# adc-optical.net
KiCad netlist of a schematic drawn in Altium Designer
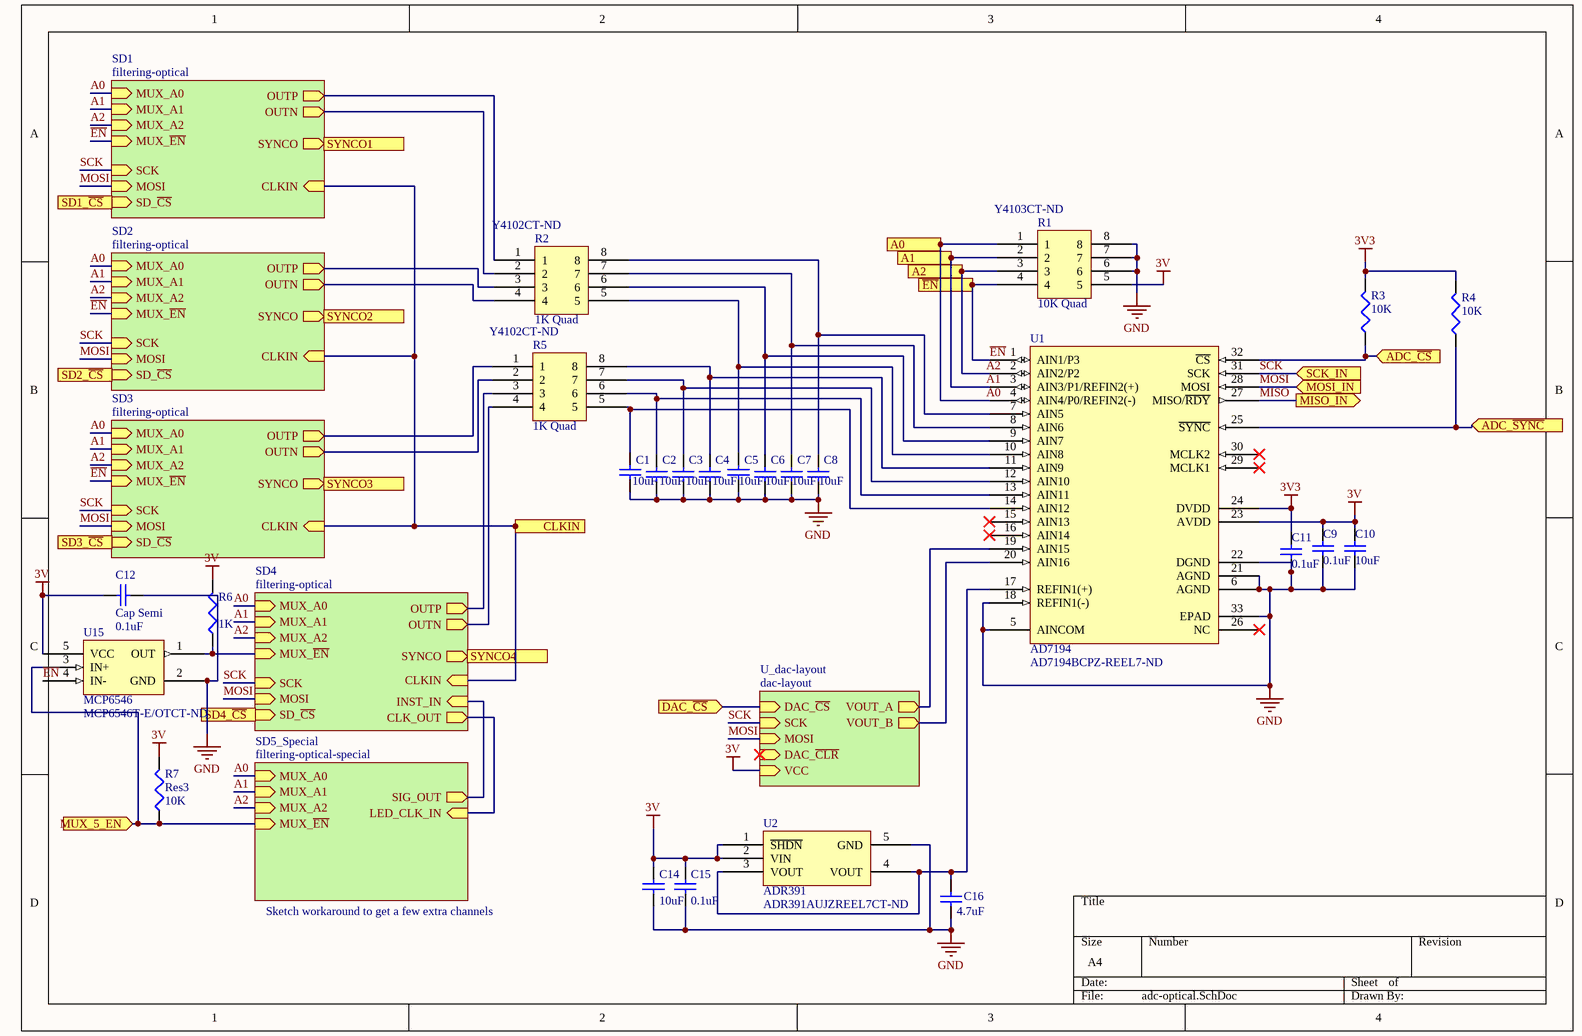
[diagram p0: adc-optical.SchDoc]

(export (version "E")
  (design (tool "Eeschema 10.0.6"))
  (components
    (comp (ref "C1")
      (value "10uF")
      (footprint "1608[0603]")
      (description "Capacitor (Semiconductor SIM Model)")
      (fields (field (name "PUBLISHER") "Altium Limited"))
      (libsource (lib "Miscellaneous Devices") (part "Cap Semi"))
    )
    (comp (ref "C2")
      (value "10uF")
      (footprint "1608[0603]")
      (description "Capacitor (Semiconductor SIM Model)")
      (fields (field (name "PUBLISHER") "Altium Limited"))
      (libsource (lib "Miscellaneous Devices") (part "Cap Semi"))
    )
    (comp (ref "C3")
      (value "10uF")
      (footprint "1608[0603]")
      (description "Capacitor (Semiconductor SIM Model)")
      (fields (field (name "PUBLISHER") "Altium Limited"))
      (libsource (lib "Miscellaneous Devices") (part "Cap Semi"))
    )
    (comp (ref "C4")
      (value "10uF")
      (footprint "1608[0603]")
      (description "Capacitor (Semiconductor SIM Model)")
      (fields (field (name "PUBLISHER") "Altium Limited"))
      (libsource (lib "Miscellaneous Devices") (part "Cap Semi"))
    )
    (comp (ref "C5")
      (value "10uF")
      (footprint "1608[0603]")
      (description "Capacitor (Semiconductor SIM Model)")
      (fields (field (name "PUBLISHER") "Altium Limited"))
      (libsource (lib "Miscellaneous Devices") (part "Cap Semi"))
    )
    (comp (ref "C6")
      (value "10uF")
      (footprint "1608[0603]")
      (description "Capacitor (Semiconductor SIM Model)")
      (fields (field (name "PUBLISHER") "Altium Limited"))
      (libsource (lib "Miscellaneous Devices") (part "Cap Semi"))
    )
    (comp (ref "C7")
      (value "10uF")
      (footprint "1608[0603]")
      (description "Capacitor (Semiconductor SIM Model)")
      (fields (field (name "PUBLISHER") "Altium Limited"))
      (libsource (lib "Miscellaneous Devices") (part "Cap Semi"))
    )
    (comp (ref "C8")
      (value "10uF")
      (footprint "1608[0603]")
      (description "Capacitor (Semiconductor SIM Model)")
      (fields (field (name "PUBLISHER") "Altium Limited"))
      (libsource (lib "Miscellaneous Devices") (part "Cap Semi"))
    )
    (comp (ref "C9")
      (value "0.1uF")
      (footprint "0402")
      (description "Capacitor (Semiconductor SIM Model)")
      (fields (field (name "PUBLISHER") "Altium Limited"))
      (libsource (lib "Miscellaneous Devices") (part "Cap Semi"))
    )
    (comp (ref "C10")
      (value "10uF")
      (footprint "1608[0603]")
      (description "Capacitor (Semiconductor SIM Model)")
      (fields (field (name "PUBLISHER") "Altium Limited"))
      (libsource (lib "Miscellaneous Devices") (part "Cap Semi"))
    )
    (comp (ref "C11")
      (value "0.1uF")
      (footprint "0402")
      (description "Capacitor (Semiconductor SIM Model)")
      (fields (field (name "PUBLISHER") "Altium Limited"))
      (libsource (lib "Miscellaneous Devices") (part "Cap Semi"))
    )
    (comp (ref "C12")
      (value "Cap Semi")
      (footprint "0402")
      (description "Capacitor (Semiconductor SIM Model)")
      (fields (field (name "ALTIUM_VALUE") "0.1uF") (field (name "PUBLISHER") "Altium Limited"))
      (libsource (lib "Miscellaneous Devices") (part "Cap Semi"))
    )
    (comp (ref "C14")
      (value "10uF")
      (footprint "1608[0603]")
      (description "Capacitor (Semiconductor SIM Model)")
      (fields (field (name "PUBLISHER") "Altium Limited"))
      (libsource (lib "Miscellaneous Devices") (part "Cap Semi"))
    )
    (comp (ref "C15")
      (value "0.1uF")
      (footprint "0402")
      (description "Capacitor (Semiconductor SIM Model)")
      (fields (field (name "PUBLISHER") "Altium Limited"))
      (libsource (lib "Miscellaneous Devices") (part "Cap Semi"))
    )
    (comp (ref "C16")
      (value "4.7uF")
      (footprint "1608[0603]")
      (description "Capacitor (Semiconductor SIM Model)")
      (fields (field (name "PUBLISHER") "Altium Limited"))
      (libsource (lib "Miscellaneous Devices") (part "Cap Semi"))
    )
    (comp (ref "R1")
      (value "10K Quad")
      (footprint "ResQuad-320X150")
      (description "Quad pack resistor")
      (fields (field (name "SUPPLIER PART NUMBER") "Y4103CT-ND"))
      (libsource (lib "PAY") (part "Res Quad Pack"))
    )
    (comp (ref "R2")
      (value "1K Quad")
      (footprint "ResQuad-320X150")
      (description "Quad pack resistor")
      (fields (field (name "SUPPLIER PART NUMBER") "Y4102CT-ND"))
      (libsource (lib "PAY") (part "Res Quad Pack"))
    )
    (comp (ref "R3")
      (value "10K")
      (footprint "0402")
      (description "Resistor")
      (fields (field (name "PUBLISHER") "Altium Limited"))
      (libsource (lib "Miscellaneous Devices") (part "Res3"))
    )
    (comp (ref "R4")
      (value "10K")
      (footprint "0402")
      (description "Resistor")
      (fields (field (name "PUBLISHER") "Altium Limited"))
      (libsource (lib "Miscellaneous Devices") (part "Res3"))
    )
    (comp (ref "R5")
      (value "1K Quad")
      (footprint "ResQuad-320X150")
      (description "Quad pack resistor")
      (fields (field (name "SUPPLIER PART NUMBER") "Y4102CT-ND"))
      (libsource (lib "PAY") (part "Res Quad Pack"))
    )
    (comp (ref "R6")
      (value "1K")
      (footprint "0402")
      (description "Resistor")
      (fields (field (name "Comment") "Res3") (field (name "PUBLISHER") "Altium Limited"))
      (libsource (lib "Miscellaneous Devices") (part "Res3"))
    )
    (comp (ref "R7")
      (value "Res3")
      (footprint "0402")
      (description "Resistor")
      (fields (field (name "ALTIUM_VALUE") "10K") (field (name "PUBLISHER") "Altium Limited"))
      (libsource (lib "Miscellaneous Devices") (part "Res3"))
    )
    (comp (ref "U1")
      (value "AD7194")
      (footprint "QFN50P500X500X100-32N")
      (description "24-bit sigma-delta ADC")
      (fields (field (name "SUPPLIER PART NUMBER 1") "AD7194BCPZ-REEL7-ND"))
      (libsource (lib "PAY") (part "AD7194"))
    )
    (comp (ref "U2")
      (value "ADR391")
      (footprint "SOT-23-5_95P290X160-5N")
      (description "2.5V reference voltage.")
      (fields (field (name "SUPPLIER PART NUMBER 1") "ADR391AUJZREEL7CT-ND"))
      (libsource (lib "PAY") (part "ADR391"))
    )
    (comp (ref "U15")
      (value "MCP6546")
      (footprint "SOT-23-5_95P290X160-5N")
      (description "Open-drain output sub-microamp comparator.")
      (fields (field (name "SUPPLIER PART NUMBER 1") "MCP6546T-E/OTCT-ND"))
      (libsource (lib "PAY") (part "MCP6546"))
    )
  )
  (nets
    (net (code "1") (name "/A0") (class "Default")
      (node (ref "R1") (pin "1") (pinfunction "1_1") (pintype "passive"))
      (node (ref "U1") (pin "4") (pinfunction "AIN4/P0/REFIN2(-)_4") (pintype "bidirectional"))
    )
    (net (code "2") (name "/A1") (class "Default")
      (node (ref "R1") (pin "2") (pinfunction "2_2") (pintype "passive"))
      (node (ref "U1") (pin "3") (pinfunction "AIN3/P1/REFIN2(+)_3") (pintype "bidirectional"))
    )
    (net (code "3") (name "/A2") (class "Default")
      (node (ref "R1") (pin "3") (pinfunction "3_3") (pintype "passive"))
      (node (ref "U1") (pin "2") (pinfunction "AIN2/P2_2") (pintype "bidirectional"))
    )
    (net (code "4") (name "/ADC_~{CS}") (class "Default")
      (node (ref "R3") (pin "1") (pinfunction "1_1") (pintype "passive"))
      (node (ref "U1") (pin "32") (pinfunction "~{CS}_32") (pintype "input"))
    )
    (net (code "5") (name "/ADC_~{SYNC}") (class "Default")
      (node (ref "R4") (pin "1") (pinfunction "1_1") (pintype "passive"))
      (node (ref "U1") (pin "25") (pinfunction "~{SYNC}_25") (pintype "input"))
    )
    (net (code "10") (name "/MISO") (class "Default")
      (node (ref "U1") (pin "27") (pinfunction "MISO/~{RDY}_27") (pintype "output"))
    )
    (net (code "11") (name "/MOSI") (class "Default")
      (node (ref "U1") (pin "28") (pinfunction "MOSI_28") (pintype "input"))
    )
    (net (code "12") (name "/MUX_5_EN") (class "Default")
      (node (ref "R7") (pin "1") (pinfunction "1_1") (pintype "passive"))
      (node (ref "U15") (pin "3") (pinfunction "IN+_3") (pintype "input"))
    )
    (net (code "13") (name "/MUX_~{EN}") (class "Default")
      (node (ref "R6") (pin "1") (pinfunction "1_1") (pintype "passive"))
      (node (ref "U15") (pin "1") (pinfunction "OUT_1") (pintype "output"))
    )
    (net (code "14") (name "/OUTN") (class "Default")
      (node (ref "R5") (pin "2") (pinfunction "2_2") (pintype "passive"))
    )
    (net (code "15") (name "/OUTN_1") (class "Default")
      (node (ref "R5") (pin "4") (pinfunction "4_4") (pintype "passive"))
    )
    (net (code "16") (name "/OUTN_2") (class "Default")
      (node (ref "R2") (pin "2") (pinfunction "2_2") (pintype "passive"))
    )
    (net (code "17") (name "/OUTN_3") (class "Default")
      (node (ref "R2") (pin "4") (pinfunction "4_4") (pintype "passive"))
    )
    (net (code "18") (name "/OUTP") (class "Default")
      (node (ref "R5") (pin "3") (pinfunction "3_3") (pintype "passive"))
    )
    (net (code "19") (name "/OUTP_1") (class "Default")
      (node (ref "R2") (pin "1") (pinfunction "1_1") (pintype "passive"))
    )
    (net (code "20") (name "/OUTP_2") (class "Default")
      (node (ref "R2") (pin "3") (pinfunction "3_3") (pintype "passive"))
    )
    (net (code "21") (name "/OUTP_3") (class "Default")
      (node (ref "R5") (pin "1") (pinfunction "1_1") (pintype "passive"))
    )
    (net (code "22") (name "/SCK") (class "Default")
      (node (ref "U1") (pin "31") (pinfunction "SCK_31") (pintype "input"))
    )
    (net (code "32") (name "/VOUT_A") (class "Default")
      (node (ref "U1") (pin "19") (pinfunction "AIN15_19") (pintype "input"))
    )
    (net (code "33") (name "/VOUT_B") (class "Default")
      (node (ref "U1") (pin "20") (pinfunction "AIN16_20") (pintype "input"))
    )
    (net (code "34") (name "/~{EN}") (class "Default")
      (node (ref "R1") (pin "4") (pinfunction "4_4") (pintype "passive"))
      (node (ref "U1") (pin "1") (pinfunction "AIN1/P3_1") (pintype "bidirectional"))
      (node (ref "U15") (pin "4") (pinfunction "IN-_4") (pintype "input"))
    )
    (net (code "35") (name "3V") (class "Default")
      (node (ref "C10") (pin "2") (pinfunction "2_2") (pintype "passive"))
      (node (ref "C12") (pin "2") (pinfunction "2_2") (pintype "passive"))
      (node (ref "C14") (pin "2") (pinfunction "2_2") (pintype "passive"))
      (node (ref "C15") (pin "2") (pinfunction "2_2") (pintype "passive"))
      (node (ref "C9") (pin "2") (pinfunction "2_2") (pintype "passive"))
      (node (ref "R1") (pin "5") (pinfunction "5_5") (pintype "passive"))
      (node (ref "R6") (pin "2") (pinfunction "2_2") (pintype "passive"))
      (node (ref "R7") (pin "2") (pinfunction "2_2") (pintype "passive"))
      (node (ref "U1") (pin "23") (pinfunction "AVDD_23") (pintype "power_in"))
      (node (ref "U15") (pin "5") (pinfunction "VCC_5") (pintype "power_in"))
      (node (ref "U2") (pin "1") (pinfunction "~{SHDN}_1") (pintype "passive"))
      (node (ref "U2") (pin "2") (pinfunction "VIN_2") (pintype "passive"))
    )
    (net (code "36") (name "3V3") (class "Default")
      (node (ref "C11") (pin "2") (pinfunction "2_2") (pintype "passive"))
      (node (ref "R3") (pin "2") (pinfunction "2_2") (pintype "passive"))
      (node (ref "R4") (pin "2") (pinfunction "2_2") (pintype "passive"))
      (node (ref "U1") (pin "24") (pinfunction "DVDD_24") (pintype "power_in"))
    )
    (net (code "37") (name "GND") (class "Default")
      (node (ref "C1") (pin "1") (pinfunction "1_1") (pintype "passive"))
      (node (ref "C10") (pin "1") (pinfunction "1_1") (pintype "passive"))
      (node (ref "C11") (pin "1") (pinfunction "1_1") (pintype "passive"))
      (node (ref "C12") (pin "1") (pinfunction "1_1") (pintype "passive"))
      (node (ref "C14") (pin "1") (pinfunction "1_1") (pintype "passive"))
      (node (ref "C15") (pin "1") (pinfunction "1_1") (pintype "passive"))
      (node (ref "C16") (pin "1") (pinfunction "1_1") (pintype "passive"))
      (node (ref "C2") (pin "1") (pinfunction "1_1") (pintype "passive"))
      (node (ref "C3") (pin "1") (pinfunction "1_1") (pintype "passive"))
      (node (ref "C4") (pin "1") (pinfunction "1_1") (pintype "passive"))
      (node (ref "C5") (pin "1") (pinfunction "1_1") (pintype "passive"))
      (node (ref "C6") (pin "1") (pinfunction "1_1") (pintype "passive"))
      (node (ref "C7") (pin "1") (pinfunction "1_1") (pintype "passive"))
      (node (ref "C8") (pin "1") (pinfunction "1_1") (pintype "passive"))
      (node (ref "C9") (pin "1") (pinfunction "1_1") (pintype "passive"))
      (node (ref "R1") (pin "6") (pinfunction "6_6") (pintype "passive"))
      (node (ref "R1") (pin "7") (pinfunction "7_7") (pintype "passive"))
      (node (ref "R1") (pin "8") (pinfunction "8_8") (pintype "passive"))
      (node (ref "U1") (pin "18") (pinfunction "REFIN1(-)_18") (pintype "input"))
      (node (ref "U1") (pin "21") (pinfunction "AGND_21") (pintype "power_in"))
      (node (ref "U1") (pin "22") (pinfunction "DGND_22") (pintype "power_in"))
      (node (ref "U1") (pin "33") (pinfunction "EPAD_33") (pintype "passive"))
      (node (ref "U1") (pin "5") (pinfunction "AINCOM_5") (pintype "power_in"))
      (node (ref "U1") (pin "6") (pinfunction "AGND_6") (pintype "power_in"))
      (node (ref "U15") (pin "2") (pinfunction "GND_2") (pintype "power_in"))
      (node (ref "U2") (pin "5") (pinfunction "GND_5") (pintype "passive"))
    )
    (net (code "38") (name "Net-(U1-AIN5)") (class "Default")
      (node (ref "C8") (pin "2") (pinfunction "2_2") (pintype "passive"))
      (node (ref "R2") (pin "8") (pinfunction "8_8") (pintype "passive"))
      (node (ref "U1") (pin "7") (pinfunction "AIN5_7") (pintype "input"))
    )
    (net (code "39") (name "Net-(U1-AIN6)") (class "Default")
      (node (ref "C7") (pin "2") (pinfunction "2_2") (pintype "passive"))
      (node (ref "R2") (pin "7") (pinfunction "7_7") (pintype "passive"))
      (node (ref "U1") (pin "8") (pinfunction "AIN6_8") (pintype "input"))
    )
    (net (code "40") (name "Net-(U1-AIN7)") (class "Default")
      (node (ref "C6") (pin "2") (pinfunction "2_2") (pintype "passive"))
      (node (ref "R2") (pin "6") (pinfunction "6_6") (pintype "passive"))
      (node (ref "U1") (pin "9") (pinfunction "AIN7_9") (pintype "input"))
    )
    (net (code "41") (name "Net-(U1-AIN8)") (class "Default")
      (node (ref "C5") (pin "2") (pinfunction "2_2") (pintype "passive"))
      (node (ref "R2") (pin "5") (pinfunction "5_5") (pintype "passive"))
      (node (ref "U1") (pin "10") (pinfunction "AIN8_10") (pintype "input"))
    )
    (net (code "42") (name "Net-(U1-AIN9)") (class "Default")
      (node (ref "C4") (pin "2") (pinfunction "2_2") (pintype "passive"))
      (node (ref "R5") (pin "8") (pinfunction "8_8") (pintype "passive"))
      (node (ref "U1") (pin "11") (pinfunction "AIN9_11") (pintype "input"))
    )
    (net (code "43") (name "Net-(U1-AIN10)") (class "Default")
      (node (ref "C3") (pin "2") (pinfunction "2_2") (pintype "passive"))
      (node (ref "R5") (pin "7") (pinfunction "7_7") (pintype "passive"))
      (node (ref "U1") (pin "12") (pinfunction "AIN10_12") (pintype "input"))
    )
    (net (code "44") (name "Net-(U1-AIN11)") (class "Default")
      (node (ref "C2") (pin "2") (pinfunction "2_2") (pintype "passive"))
      (node (ref "R5") (pin "6") (pinfunction "6_6") (pintype "passive"))
      (node (ref "U1") (pin "13") (pinfunction "AIN11_13") (pintype "input"))
    )
    (net (code "45") (name "Net-(U1-AIN12)") (class "Default")
      (node (ref "C1") (pin "2") (pinfunction "2_2") (pintype "passive"))
      (node (ref "R5") (pin "5") (pinfunction "5_5") (pintype "passive"))
      (node (ref "U1") (pin "14") (pinfunction "AIN12_14") (pintype "input"))
    )
    (net (code "46") (name "Net-(U1-REFIN1(+))") (class "Default")
      (node (ref "C16") (pin "2") (pinfunction "2_2") (pintype "passive"))
      (node (ref "U1") (pin "17") (pinfunction "REFIN1(+)_17") (pintype "input"))
      (node (ref "U2") (pin "3") (pinfunction "VOUT_3") (pintype "passive"))
      (node (ref "U2") (pin "4") (pinfunction "VOUT_4") (pintype "passive"))
    )
    (net (code "47") (name "unconnected-(U1-AIN13-Pad15)") (class "Default")
      (node (ref "U1") (pin "15") (pinfunction "AIN13_15") (pintype "input+no_connect"))
    )
    (net (code "48") (name "unconnected-(U1-AIN14-Pad16)") (class "Default")
      (node (ref "U1") (pin "16") (pinfunction "AIN14_16") (pintype "input+no_connect"))
    )
    (net (code "49") (name "unconnected-(U1-MCLK1-Pad29)") (class "Default")
      (node (ref "U1") (pin "29") (pinfunction "MCLK1_29") (pintype "input+no_connect"))
    )
    (net (code "50") (name "unconnected-(U1-MCLK2-Pad30)") (class "Default")
      (node (ref "U1") (pin "30") (pinfunction "MCLK2_30") (pintype "input+no_connect"))
    )
    (net (code "51") (name "unconnected-(U1-NC-Pad26)") (class "Default")
      (node (ref "U1") (pin "26") (pinfunction "NC_26") (pintype "passive+no_connect"))
    )
  )
)
